# main.net
KiCad netlist of a schematic drawn in EAGLE
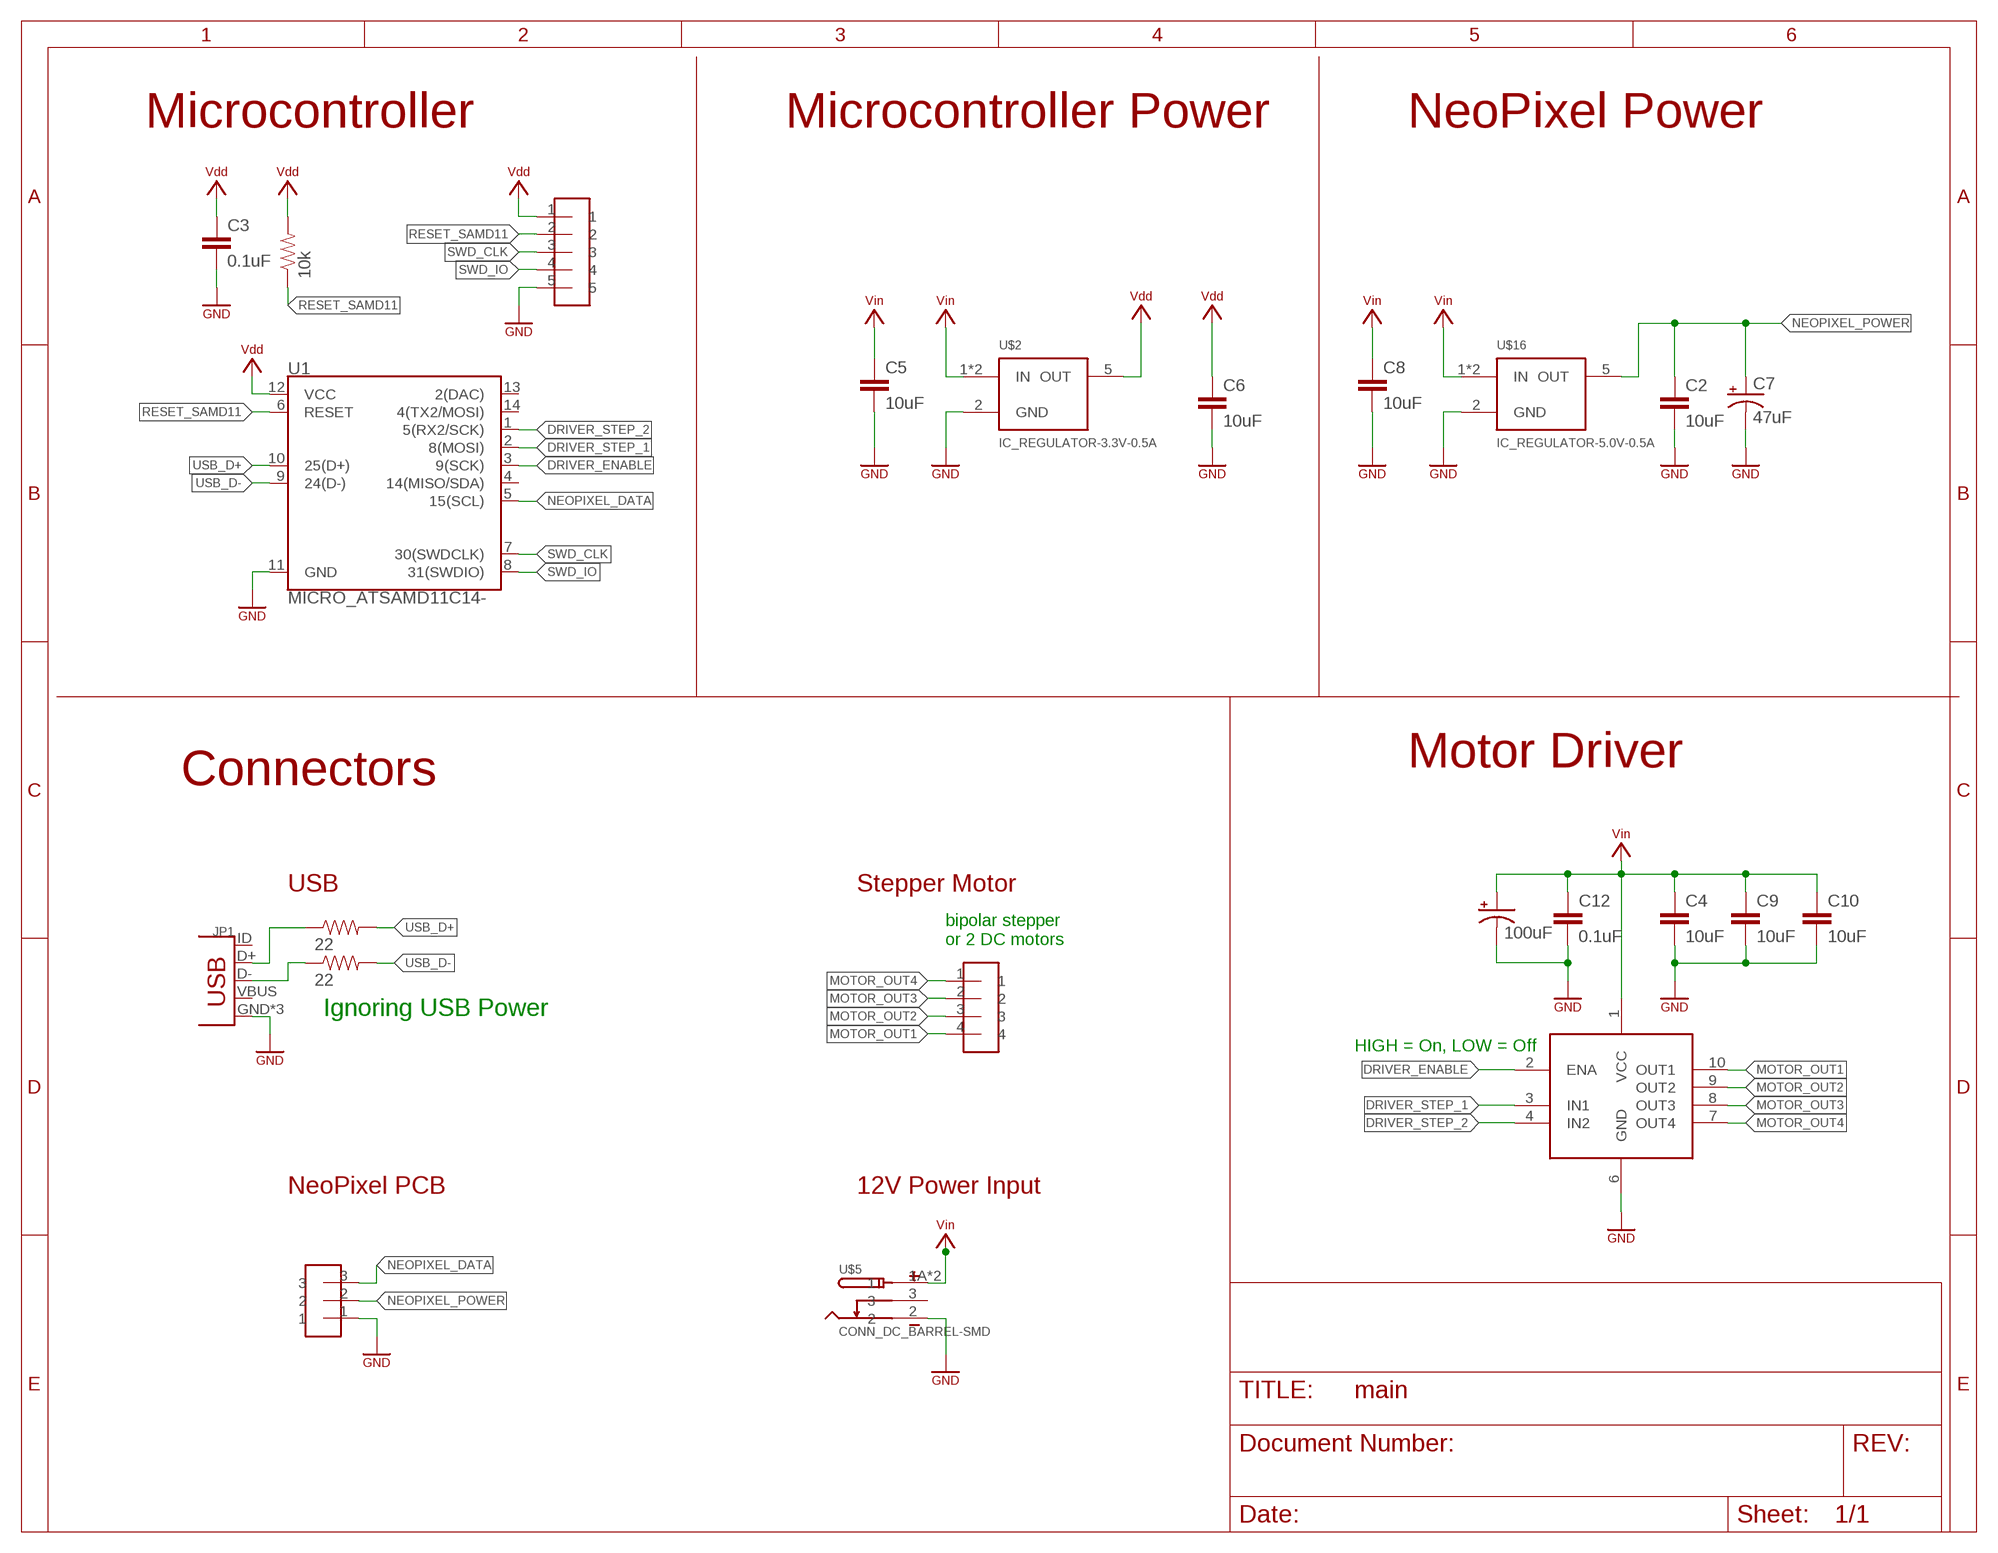
[diagram p0: schematic, sheet 1]

(export (version "E")
  (design (tool "Eeschema 10.0.6"))
  (components
    (comp (ref "C1")
      (value "100uF")
      (footprint "eagle-import:CAP_RADIAL_CAN_8MM")
      (libsource (lib "eagle-import") (part "COMPONENT_CAP_POL-8MM"))
    )
    (comp (ref "C2")
      (value "10uF")
      (footprint "eagle-import:0805")
      (libsource (lib "eagle-import") (part "COMPONENT_CAP-0805"))
    )
    (comp (ref "C3")
      (value "0.1uF")
      (footprint "eagle-import:0805")
      (libsource (lib "eagle-import") (part "COMPONENT_CAP-0805"))
    )
    (comp (ref "C4")
      (value "10uF")
      (footprint "eagle-import:0805")
      (libsource (lib "eagle-import") (part "COMPONENT_CAP-0805"))
    )
    (comp (ref "C5")
      (value "10uF")
      (footprint "eagle-import:0805")
      (libsource (lib "eagle-import") (part "COMPONENT_CAP-0805"))
    )
    (comp (ref "C6")
      (value "10uF")
      (footprint "eagle-import:0805")
      (libsource (lib "eagle-import") (part "COMPONENT_CAP-0805"))
    )
    (comp (ref "C7")
      (value "47uF")
      (footprint "eagle-import:CAP_RADIAL_CAN_6.3MM")
      (libsource (lib "eagle-import") (part "COMPONENT_CAP_POL-6.3MM"))
    )
    (comp (ref "C8")
      (value "10uF")
      (footprint "eagle-import:0805")
      (libsource (lib "eagle-import") (part "COMPONENT_CAP-0805"))
    )
    (comp (ref "C9")
      (value "10uF")
      (footprint "eagle-import:0805")
      (libsource (lib "eagle-import") (part "COMPONENT_CAP-0805"))
    )
    (comp (ref "C10")
      (value "10uF")
      (footprint "eagle-import:0805")
      (libsource (lib "eagle-import") (part "COMPONENT_CAP-0805"))
    )
    (comp (ref "C12")
      (value "0.1uF")
      (footprint "eagle-import:0805")
      (libsource (lib "eagle-import") (part "COMPONENT_CAP-0805"))
    )
    (comp (ref "JP1")
      (value "CONN_USB-10118192-0001LF")
      (footprint "eagle-import:USB-MICRO-FEMALE")
      (libsource (lib "eagle-import") (part "CONN_USB-10118192-0001LF"))
    )
    (comp (ref "R1")
      (value "10k")
      (footprint "eagle-import:0805")
      (libsource (lib "eagle-import") (part "COMPONENT_RESISTOR-0805"))
    )
    (comp (ref "R2")
      (value "22")
      (footprint "eagle-import:0805")
      (libsource (lib "eagle-import") (part "COMPONENT_RESISTOR-0805"))
    )
    (comp (ref "R3")
      (value "22")
      (footprint "eagle-import:0805")
      (libsource (lib "eagle-import") (part "COMPONENT_RESISTOR-0805"))
    )
    (comp (ref "U$1")
      (value "HEADER-4-HORIZONTAL")
      (footprint "eagle-import:HEADER-4-HORIZONTAL")
      (libsource (lib "eagle-import") (part "HEADER-4-HORIZONTAL"))
    )
    (comp (ref "U$2")
      (value "IC_REGULATOR-3.3V-0.5A")
      (footprint "eagle-import:SOT23-5")
      (libsource (lib "eagle-import") (part "IC_REGULATOR-3.3V-0.5A"))
    )
    (comp (ref "U$3")
      (value "IC_H_BRIDGE_LV8549MC")
      (footprint "eagle-import:SOIC10")
      (libsource (lib "eagle-import") (part "IC_H_BRIDGE_LV8549MC"))
    )
    (comp (ref "U$5")
      (value "CONN_DC_BARREL-SMD")
      (footprint "eagle-import:694106106102")
      (libsource (lib "eagle-import") (part "CONN_DC_BARREL-SMD"))
    )
    (comp (ref "U$10")
      (value "HEADER-5-TESTPOINT")
      (footprint "eagle-import:TESTPOINT-5")
      (libsource (lib "eagle-import") (part "HEADER-5-TESTPOINT"))
    )
    (comp (ref "U$16")
      (value "IC_REGULATOR-5.0V-0.5A")
      (footprint "eagle-import:SOT23-5")
      (libsource (lib "eagle-import") (part "IC_REGULATOR-5.0V-0.5A"))
    )
    (comp (ref "U$17")
      (value "HEADER-3-HORIZONTAL")
      (footprint "eagle-import:HEADER-3-HORIZONTAL")
      (libsource (lib "eagle-import") (part "HEADER-3-HORIZONTAL"))
    )
    (comp (ref "U1")
      (value "MICRO_ATSAMD11C14-")
      (footprint "eagle-import:SOIC14")
      (libsource (lib "eagle-import") (part "MICRO_ATSAMD11C14-"))
    )
  )
  (nets
    (net (code "1") (name "DRIVER_ENABLE") (class "Default")
      (node (ref "U$3") (pin "2") (pinfunction "ENA_2") (pintype "bidirectional"))
      (node (ref "U1") (pin "3") (pinfunction "9(SCK)_3") (pintype "bidirectional"))
    )
    (net (code "2") (name "DRIVER_STEP_1") (class "Default")
      (node (ref "U$3") (pin "3") (pinfunction "IN1_3") (pintype "bidirectional"))
      (node (ref "U1") (pin "2") (pinfunction "8(MOSI)_2") (pintype "bidirectional"))
    )
    (net (code "3") (name "DRIVER_STEP_2") (class "Default")
      (node (ref "U$3") (pin "4") (pinfunction "IN2_4") (pintype "bidirectional"))
      (node (ref "U1") (pin "1") (pinfunction "5(RX2/SCK)_1") (pintype "bidirectional"))
    )
    (net (code "4") (name "MOTOR_OUT1") (class "Default")
      (node (ref "U$1") (pin "4") (pinfunction "4_4") (pintype "bidirectional"))
      (node (ref "U$3") (pin "10") (pinfunction "OUT1_10") (pintype "bidirectional"))
    )
    (net (code "5") (name "MOTOR_OUT2") (class "Default")
      (node (ref "U$1") (pin "3") (pinfunction "3_3") (pintype "bidirectional"))
      (node (ref "U$3") (pin "9") (pinfunction "OUT2_9") (pintype "bidirectional"))
    )
    (net (code "6") (name "MOTOR_OUT3") (class "Default")
      (node (ref "U$1") (pin "2") (pinfunction "2_2") (pintype "bidirectional"))
      (node (ref "U$3") (pin "8") (pinfunction "OUT3_8") (pintype "bidirectional"))
    )
    (net (code "7") (name "MOTOR_OUT4") (class "Default")
      (node (ref "U$1") (pin "1") (pinfunction "1_1") (pintype "bidirectional"))
      (node (ref "U$3") (pin "7") (pinfunction "OUT4_7") (pintype "bidirectional"))
    )
    (net (code "8") (name "NEOPIXEL_DATA") (class "Default")
      (node (ref "U$17") (pin "3") (pinfunction "3_3") (pintype "bidirectional"))
      (node (ref "U1") (pin "5") (pinfunction "15(SCL)_5") (pintype "bidirectional"))
    )
    (net (code "9") (name "NEOPIXEL_POWER") (class "Default")
      (node (ref "C2") (pin "1") (pinfunction "1_1") (pintype "passive"))
      (node (ref "C7") (pin "+") (pinfunction "+_+") (pintype "passive"))
      (node (ref "U$16") (pin "5") (pinfunction "OUT_5") (pintype "bidirectional"))
      (node (ref "U$17") (pin "2") (pinfunction "2_2") (pintype "bidirectional"))
    )
    (net (code "10") (name "Net-(JP1-PadD+)") (class "Default")
      (node (ref "JP1") (pin "D+") (pinfunction "D+_D+") (pintype "bidirectional"))
      (node (ref "R2") (pin "1") (pinfunction "1_1") (pintype "passive"))
    )
    (net (code "11") (name "Net-(JP1-PadD-)") (class "Default")
      (node (ref "JP1") (pin "D-") (pinfunction "D-_D-") (pintype "bidirectional"))
      (node (ref "R3") (pin "1") (pinfunction "1_1") (pintype "passive"))
    )
    (net (code "12") (name "RESET_SAMD11") (class "Default")
      (node (ref "R1") (pin "1") (pinfunction "1_1") (pintype "passive"))
      (node (ref "U$10") (pin "2") (pinfunction "2_2") (pintype "bidirectional"))
      (node (ref "U1") (pin "6") (pinfunction "RESET_6") (pintype "bidirectional"))
    )
    (net (code "13") (name "SWD_CLK") (class "Default")
      (node (ref "U$10") (pin "3") (pinfunction "3_3") (pintype "bidirectional"))
      (node (ref "U1") (pin "7") (pinfunction "30(SWDCLK)_7") (pintype "bidirectional"))
    )
    (net (code "14") (name "SWD_IO") (class "Default")
      (node (ref "U$10") (pin "4") (pinfunction "4_4") (pintype "bidirectional"))
      (node (ref "U1") (pin "8") (pinfunction "31(SWDIO)_8") (pintype "bidirectional"))
    )
    (net (code "15") (name "SYMBOL_GND") (class "Default")
      (node (ref "C1") (pin "-") (pinfunction "-_-") (pintype "passive"))
      (node (ref "C10") (pin "2") (pinfunction "2_2") (pintype "passive"))
      (node (ref "C12") (pin "2") (pinfunction "2_2") (pintype "passive"))
      (node (ref "C2") (pin "2") (pinfunction "2_2") (pintype "passive"))
      (node (ref "C3") (pin "2") (pinfunction "2_2") (pintype "passive"))
      (node (ref "C4") (pin "2") (pinfunction "2_2") (pintype "passive"))
      (node (ref "C5") (pin "2") (pinfunction "2_2") (pintype "passive"))
      (node (ref "C6") (pin "2") (pinfunction "2_2") (pintype "passive"))
      (node (ref "C7") (pin "-") (pinfunction "-_-") (pintype "passive"))
      (node (ref "C8") (pin "2") (pinfunction "2_2") (pintype "passive"))
      (node (ref "C9") (pin "2") (pinfunction "2_2") (pintype "passive"))
      (node (ref "JP1") (pin "GND") (pinfunction "GND_GND") (pintype "bidirectional"))
      (node (ref "JP1") (pin "MT1") (pinfunction "GND_MT1") (pintype "bidirectional"))
      (node (ref "JP1") (pin "MT2") (pinfunction "GND_MT2") (pintype "bidirectional"))
      (node (ref "U$10") (pin "5") (pinfunction "5_5") (pintype "bidirectional"))
      (node (ref "U$16") (pin "2") (pinfunction "GND_2") (pintype "bidirectional"))
      (node (ref "U$17") (pin "1") (pinfunction "1_1") (pintype "bidirectional"))
      (node (ref "U$2") (pin "2") (pinfunction "GND_2") (pintype "bidirectional"))
      (node (ref "U$3") (pin "6") (pinfunction "GND_6") (pintype "bidirectional"))
      (node (ref "U$5") (pin "2") (pinfunction "2_2") (pintype "bidirectional"))
      (node (ref "U1") (pin "11") (pinfunction "GND_11") (pintype "bidirectional"))
    )
    (net (code "16") (name "SYMBOL_VDD") (class "Default")
      (node (ref "C3") (pin "1") (pinfunction "1_1") (pintype "passive"))
      (node (ref "C6") (pin "1") (pinfunction "1_1") (pintype "passive"))
      (node (ref "R1") (pin "2") (pinfunction "2_2") (pintype "passive"))
      (node (ref "U$10") (pin "1") (pinfunction "1_1") (pintype "bidirectional"))
      (node (ref "U$2") (pin "5") (pinfunction "OUT_5") (pintype "bidirectional"))
      (node (ref "U1") (pin "12") (pinfunction "VCC_12") (pintype "bidirectional"))
    )
    (net (code "17") (name "SYMBOL_VIN") (class "Default")
      (node (ref "C1") (pin "+") (pinfunction "+_+") (pintype "passive"))
      (node (ref "C10") (pin "1") (pinfunction "1_1") (pintype "passive"))
      (node (ref "C12") (pin "1") (pinfunction "1_1") (pintype "passive"))
      (node (ref "C4") (pin "1") (pinfunction "1_1") (pintype "passive"))
      (node (ref "C5") (pin "1") (pinfunction "1_1") (pintype "passive"))
      (node (ref "C8") (pin "1") (pinfunction "1_1") (pintype "passive"))
      (node (ref "C9") (pin "1") (pinfunction "1_1") (pintype "passive"))
      (node (ref "U$16") (pin "1") (pinfunction "IN_1") (pintype "bidirectional"))
      (node (ref "U$16") (pin "3") (pinfunction "IN_3") (pintype "bidirectional"))
      (node (ref "U$2") (pin "1") (pinfunction "IN_1") (pintype "bidirectional"))
      (node (ref "U$2") (pin "3") (pinfunction "IN_3") (pintype "bidirectional"))
      (node (ref "U$3") (pin "1") (pinfunction "VCC_1") (pintype "bidirectional"))
      (node (ref "U$5") (pin "1A") (pinfunction "1_1A") (pintype "bidirectional"))
      (node (ref "U$5") (pin "1B") (pinfunction "1_1B") (pintype "bidirectional"))
    )
    (net (code "18") (name "USB_D+") (class "Default")
      (node (ref "R2") (pin "2") (pinfunction "2_2") (pintype "passive"))
      (node (ref "U1") (pin "10") (pinfunction "25(D+)_10") (pintype "bidirectional"))
    )
    (net (code "19") (name "USB_D-") (class "Default")
      (node (ref "R3") (pin "2") (pinfunction "2_2") (pintype "passive"))
      (node (ref "U1") (pin "9") (pinfunction "24(D-)_9") (pintype "bidirectional"))
    )
    (net (code "20") (name "unconnected-(JP1-PadVBUS)") (class "Default")
      (node (ref "JP1") (pin "VBUS") (pinfunction "VBUS_VBUS") (pintype "bidirectional"))
    )
    (net (code "21") (name "unconnected-(JP1-SHIELD-PadID)") (class "Default")
      (node (ref "JP1") (pin "ID") (pinfunction "SHIELD_ID") (pintype "bidirectional"))
    )
    (net (code "22") (name "unconnected-(U$5-Pad3)") (class "Default")
      (node (ref "U$5") (pin "3") (pinfunction "3_3") (pintype "bidirectional"))
    )
    (net (code "23") (name "unconnected-(U1-2(DAC)-Pad13)") (class "Default")
      (node (ref "U1") (pin "13") (pinfunction "2(DAC)_13") (pintype "bidirectional"))
    )
    (net (code "24") (name "unconnected-(U1-4(TX2{slash}MOSI)-Pad14)") (class "Default")
      (node (ref "U1") (pin "14") (pinfunction "4(TX2/MOSI)_14") (pintype "bidirectional"))
    )
    (net (code "25") (name "unconnected-(U1-14(MISO{slash}SDA)-Pad4)") (class "Default")
      (node (ref "U1") (pin "4") (pinfunction "14(MISO/SDA)_4") (pintype "bidirectional"))
    )
  )
)
